# 7seg.net
KiCad netlist of a schematic drawn in EAGLE
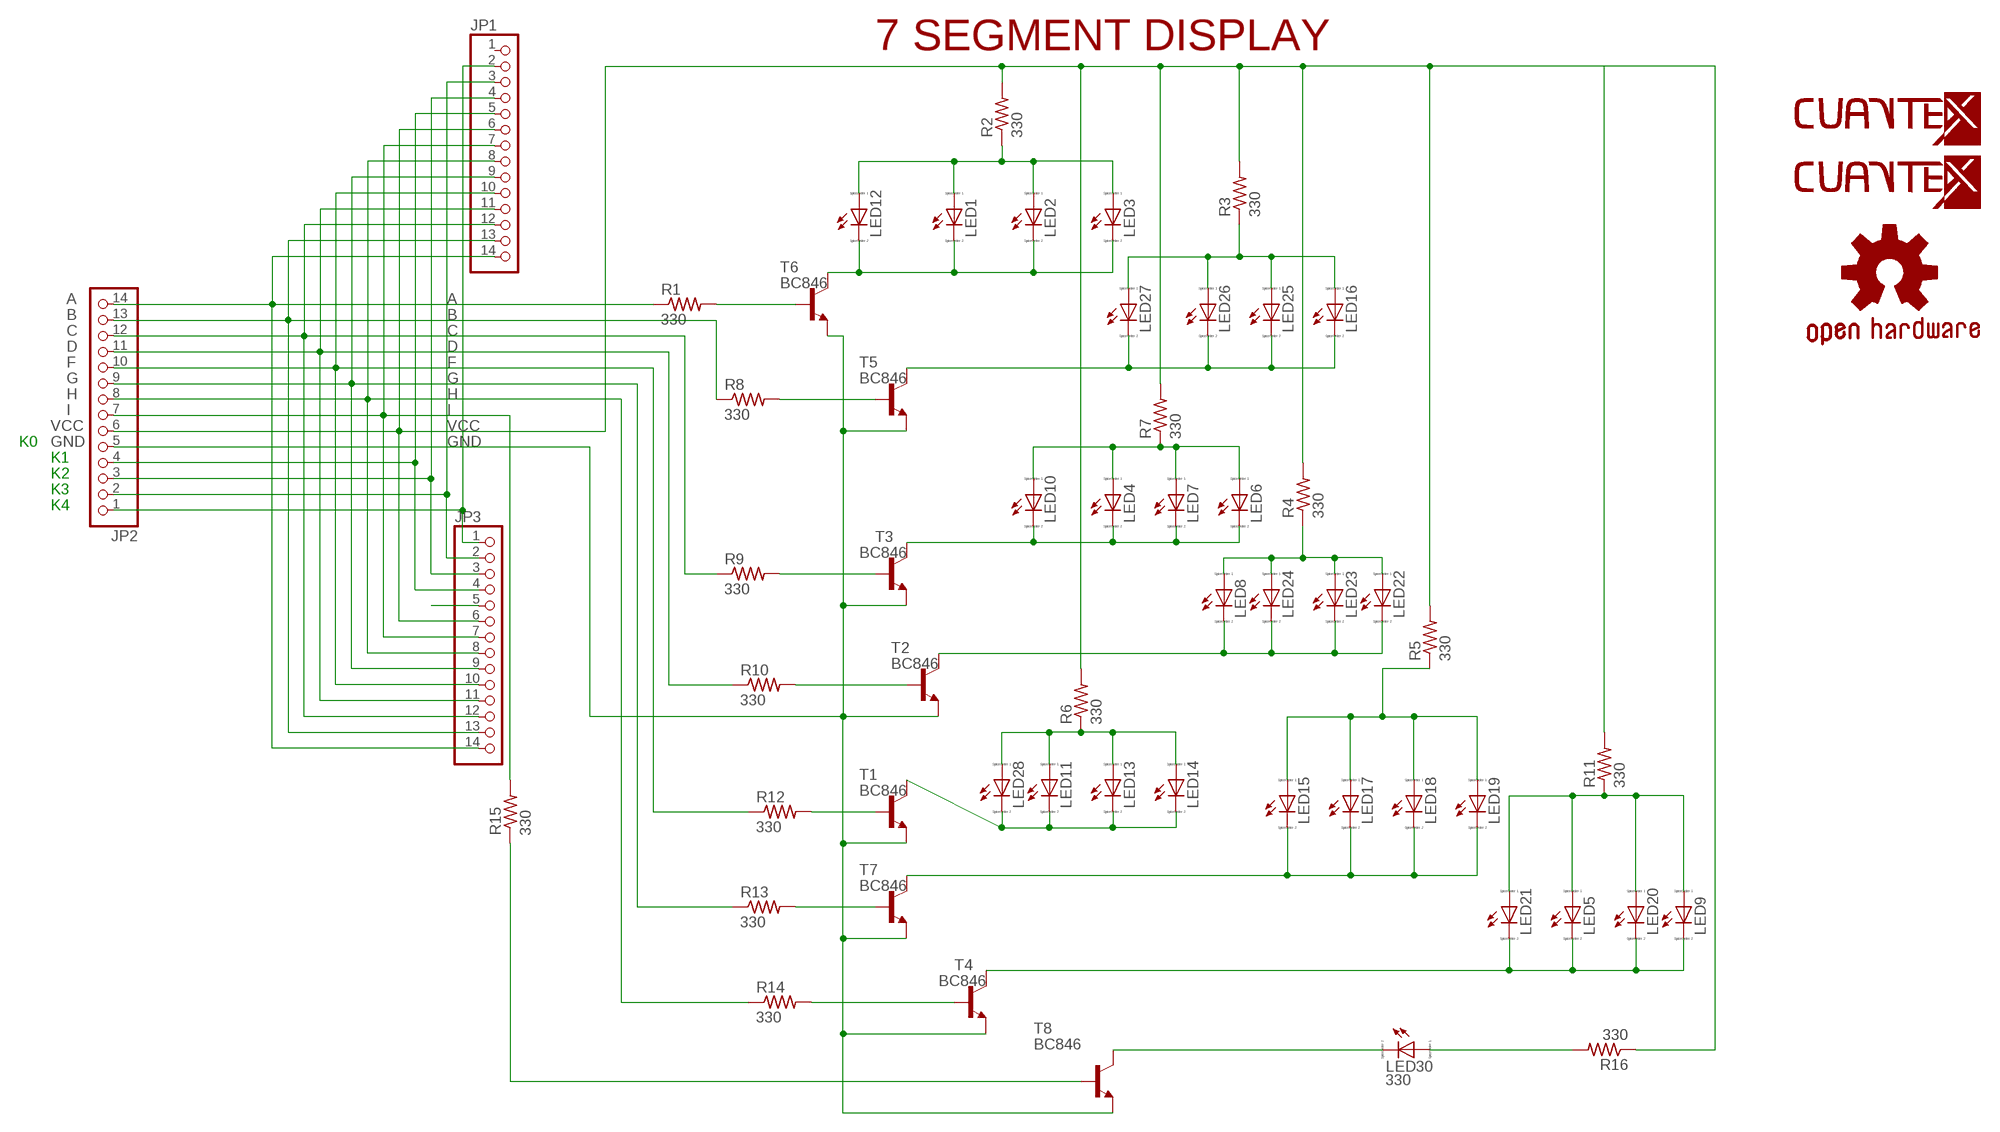
[diagram p0: schematic, sheet 1]

(export (version "E")
  (design (tool "Eeschema 10.0.6"))
  (components
    (comp (ref "GOLD_ORB_SM2")
      (value "OSHWLOGO_GOLD_ORB_MED")
      (footprint "eagle-import:OSHW1")
      (libsource (lib "eagle-import") (part "OSHWLOGO_GOLD_ORB_MED"))
    )
    (comp (ref "JP1")
      (value "PINHD-1X14")
      (footprint "eagle-import:1X14")
      (libsource (lib "eagle-import") (part "PINHD-1X14"))
    )
    (comp (ref "JP2")
      (value "PINHD-1X14")
      (footprint "eagle-import:1X14")
      (libsource (lib "eagle-import") (part "PINHD-1X14"))
    )
    (comp (ref "JP3")
      (value "PINHD-1X14")
      (footprint "eagle-import:1X14")
      (libsource (lib "eagle-import") (part "PINHD-1X14"))
    )
    (comp (ref "LED1")
      (value "LED_E")
      (footprint "eagle-import:LED_1206")
      (libsource (lib "eagle-import") (part "LED_E"))
    )
    (comp (ref "LED2")
      (value "LED_E")
      (footprint "eagle-import:LED_1206")
      (libsource (lib "eagle-import") (part "LED_E"))
    )
    (comp (ref "LED3")
      (value "LED_E")
      (footprint "eagle-import:LED_1206")
      (libsource (lib "eagle-import") (part "LED_E"))
    )
    (comp (ref "LED4")
      (value "LED_E")
      (footprint "eagle-import:LED_1206")
      (libsource (lib "eagle-import") (part "LED_E"))
    )
    (comp (ref "LED5")
      (value "LED_E")
      (footprint "eagle-import:LED_1206")
      (libsource (lib "eagle-import") (part "LED_E"))
    )
    (comp (ref "LED6")
      (value "LED_E")
      (footprint "eagle-import:LED_1206")
      (libsource (lib "eagle-import") (part "LED_E"))
    )
    (comp (ref "LED7")
      (value "LED_E")
      (footprint "eagle-import:LED_1206")
      (libsource (lib "eagle-import") (part "LED_E"))
    )
    (comp (ref "LED8")
      (value "LED_E")
      (footprint "eagle-import:LED_1206")
      (libsource (lib "eagle-import") (part "LED_E"))
    )
    (comp (ref "LED9")
      (value "LED_E")
      (footprint "eagle-import:LED_1206")
      (libsource (lib "eagle-import") (part "LED_E"))
    )
    (comp (ref "LED10")
      (value "LED_E")
      (footprint "eagle-import:LED_1206")
      (libsource (lib "eagle-import") (part "LED_E"))
    )
    (comp (ref "LED11")
      (value "LED_E")
      (footprint "eagle-import:LED_1206")
      (libsource (lib "eagle-import") (part "LED_E"))
    )
    (comp (ref "LED12")
      (value "LED_E")
      (footprint "eagle-import:LED_1206")
      (libsource (lib "eagle-import") (part "LED_E"))
    )
    (comp (ref "LED13")
      (value "LED_E")
      (footprint "eagle-import:LED_1206")
      (libsource (lib "eagle-import") (part "LED_E"))
    )
    (comp (ref "LED14")
      (value "LED_E")
      (footprint "eagle-import:LED_1206")
      (libsource (lib "eagle-import") (part "LED_E"))
    )
    (comp (ref "LED15")
      (value "LED_E")
      (footprint "eagle-import:LED_1206")
      (libsource (lib "eagle-import") (part "LED_E"))
    )
    (comp (ref "LED16")
      (value "LED_E")
      (footprint "eagle-import:LED_1206")
      (libsource (lib "eagle-import") (part "LED_E"))
    )
    (comp (ref "LED17")
      (value "LED_E")
      (footprint "eagle-import:LED_1206")
      (libsource (lib "eagle-import") (part "LED_E"))
    )
    (comp (ref "LED18")
      (value "LED_E")
      (footprint "eagle-import:LED_1206")
      (libsource (lib "eagle-import") (part "LED_E"))
    )
    (comp (ref "LED19")
      (value "LED_E")
      (footprint "eagle-import:LED_1206")
      (libsource (lib "eagle-import") (part "LED_E"))
    )
    (comp (ref "LED20")
      (value "LED_E")
      (footprint "eagle-import:LED_1206")
      (libsource (lib "eagle-import") (part "LED_E"))
    )
    (comp (ref "LED21")
      (value "LED_E")
      (footprint "eagle-import:LED_1206")
      (libsource (lib "eagle-import") (part "LED_E"))
    )
    (comp (ref "LED22")
      (value "LED_E")
      (footprint "eagle-import:LED_1206")
      (libsource (lib "eagle-import") (part "LED_E"))
    )
    (comp (ref "LED23")
      (value "LED_E")
      (footprint "eagle-import:LED_1206")
      (libsource (lib "eagle-import") (part "LED_E"))
    )
    (comp (ref "LED24")
      (value "LED_E")
      (footprint "eagle-import:LED_1206")
      (libsource (lib "eagle-import") (part "LED_E"))
    )
    (comp (ref "LED25")
      (value "LED_E")
      (footprint "eagle-import:LED_1206")
      (libsource (lib "eagle-import") (part "LED_E"))
    )
    (comp (ref "LED26")
      (value "LED_E")
      (footprint "eagle-import:LED_1206")
      (libsource (lib "eagle-import") (part "LED_E"))
    )
    (comp (ref "LED27")
      (value "LED_E")
      (footprint "eagle-import:LED_1206")
      (libsource (lib "eagle-import") (part "LED_E"))
    )
    (comp (ref "LED28")
      (value "LED_E")
      (footprint "eagle-import:LED_1206")
      (libsource (lib "eagle-import") (part "LED_E"))
    )
    (comp (ref "LED30")
      (value "330")
      (footprint "eagle-import:LED_1206")
      (libsource (lib "eagle-import") (part "LED_E"))
    )
    (comp (ref "R1")
      (value "330")
      (footprint "eagle-import:R0603")
      (libsource (lib "eagle-import") (part "resistor_R-US_R0603"))
    )
    (comp (ref "R2")
      (value "330")
      (footprint "eagle-import:R0603")
      (libsource (lib "eagle-import") (part "resistor_R-US_R0603"))
    )
    (comp (ref "R3")
      (value "330")
      (footprint "eagle-import:R0603")
      (libsource (lib "eagle-import") (part "resistor_R-US_R0603"))
    )
    (comp (ref "R4")
      (value "330")
      (footprint "eagle-import:R0603")
      (libsource (lib "eagle-import") (part "resistor_R-US_R0603"))
    )
    (comp (ref "R5")
      (value "330")
      (footprint "eagle-import:R0603")
      (libsource (lib "eagle-import") (part "resistor_R-US_R0603"))
    )
    (comp (ref "R6")
      (value "330")
      (footprint "eagle-import:R0603")
      (libsource (lib "eagle-import") (part "resistor_R-US_R0603"))
    )
    (comp (ref "R7")
      (value "330")
      (footprint "eagle-import:R0603")
      (libsource (lib "eagle-import") (part "resistor_R-US_R0603"))
    )
    (comp (ref "R8")
      (value "330")
      (footprint "eagle-import:R0603")
      (libsource (lib "eagle-import") (part "resistor_R-US_R0603"))
    )
    (comp (ref "R9")
      (value "330")
      (footprint "eagle-import:R0603")
      (libsource (lib "eagle-import") (part "resistor_R-US_R0603"))
    )
    (comp (ref "R10")
      (value "330")
      (footprint "eagle-import:R0603")
      (libsource (lib "eagle-import") (part "resistor_R-US_R0603"))
    )
    (comp (ref "R11")
      (value "330")
      (footprint "eagle-import:R0603")
      (libsource (lib "eagle-import") (part "resistor_R-US_R0603"))
    )
    (comp (ref "R12")
      (value "330")
      (footprint "eagle-import:R0603")
      (libsource (lib "eagle-import") (part "resistor_R-US_R0603"))
    )
    (comp (ref "R13")
      (value "330")
      (footprint "eagle-import:R0603")
      (libsource (lib "eagle-import") (part "resistor_R-US_R0603"))
    )
    (comp (ref "R14")
      (value "330")
      (footprint "eagle-import:R0603")
      (libsource (lib "eagle-import") (part "resistor_R-US_R0603"))
    )
    (comp (ref "R15")
      (value "330")
      (footprint "eagle-import:R0603")
      (libsource (lib "eagle-import") (part "R-US_R0603"))
    )
    (comp (ref "R16")
      (value "330")
      (footprint "eagle-import:R0603")
      (libsource (lib "eagle-import") (part "R-US_R0603"))
    )
    (comp (ref "T1")
      (value "BC846")
      (footprint "eagle-import:SOT23")
      (libsource (lib "eagle-import") (part "BC846"))
    )
    (comp (ref "T2")
      (value "BC846")
      (footprint "eagle-import:SOT23")
      (libsource (lib "eagle-import") (part "transistor-neu-to92_BC846"))
    )
    (comp (ref "T3")
      (value "BC846")
      (footprint "eagle-import:SOT23")
      (libsource (lib "eagle-import") (part "transistor-neu-to92_BC846"))
    )
    (comp (ref "T4")
      (value "BC846")
      (footprint "eagle-import:SOT23")
      (libsource (lib "eagle-import") (part "transistor-neu-to92_BC846"))
    )
    (comp (ref "T5")
      (value "BC846")
      (footprint "eagle-import:SOT23")
      (libsource (lib "eagle-import") (part "transistor-neu-to92_BC846"))
    )
    (comp (ref "T6")
      (value "BC846")
      (footprint "eagle-import:SOT23")
      (libsource (lib "eagle-import") (part "transistor-neu-to92_BC846"))
    )
    (comp (ref "T7")
      (value "BC846")
      (footprint "eagle-import:SOT23")
      (libsource (lib "eagle-import") (part "transistor-neu-to92_BC846"))
    )
    (comp (ref "T8")
      (value "BC846")
      (footprint "eagle-import:SOT23")
      (libsource (lib "eagle-import") (part "transistor-neu-to92_BC846"))
    )
    (comp (ref "U$1")
      (value "LOGO-TOP-20MM")
      (footprint "eagle-import:C-0")
      (libsource (lib "eagle-import") (part "LOGO-TOP-20MM"))
    )
    (comp (ref "U$2")
      (value "LOGO-BOT-60MM")
      (footprint "eagle-import:B-60")
      (libsource (lib "eagle-import") (part "LOGO-BOT-60MM"))
    )
  )
  (nets
    (net (code "1") (name "/A") (class "Default")
      (node (ref "JP1") (pin "14") (pinfunction "14_14") (pintype "passive"))
      (node (ref "JP2") (pin "14") (pinfunction "14_14") (pintype "passive"))
      (node (ref "JP3") (pin "14") (pinfunction "14_14") (pintype "passive"))
      (node (ref "R1") (pin "1") (pinfunction "1_1") (pintype "passive"))
    )
    (net (code "2") (name "/B") (class "Default")
      (node (ref "JP1") (pin "13") (pinfunction "13_13") (pintype "passive"))
      (node (ref "JP2") (pin "13") (pinfunction "13_13") (pintype "passive"))
      (node (ref "JP3") (pin "13") (pinfunction "13_13") (pintype "passive"))
      (node (ref "R8") (pin "1") (pinfunction "1_1") (pintype "passive"))
    )
    (net (code "3") (name "/C") (class "Default")
      (node (ref "JP1") (pin "12") (pinfunction "12_12") (pintype "passive"))
      (node (ref "JP2") (pin "12") (pinfunction "12_12") (pintype "passive"))
      (node (ref "JP3") (pin "12") (pinfunction "12_12") (pintype "passive"))
      (node (ref "R9") (pin "1") (pinfunction "1_1") (pintype "passive"))
    )
    (net (code "4") (name "/D") (class "Default")
      (node (ref "JP1") (pin "11") (pinfunction "11_11") (pintype "passive"))
      (node (ref "JP2") (pin "11") (pinfunction "11_11") (pintype "passive"))
      (node (ref "JP3") (pin "11") (pinfunction "11_11") (pintype "passive"))
      (node (ref "R10") (pin "1") (pinfunction "1_1") (pintype "passive"))
    )
    (net (code "5") (name "/F") (class "Default")
      (node (ref "JP1") (pin "10") (pinfunction "10_10") (pintype "passive"))
      (node (ref "JP2") (pin "10") (pinfunction "10_10") (pintype "passive"))
      (node (ref "JP3") (pin "10") (pinfunction "10_10") (pintype "passive"))
      (node (ref "R12") (pin "1") (pinfunction "1_1") (pintype "passive"))
    )
    (net (code "6") (name "/G") (class "Default")
      (node (ref "JP1") (pin "9") (pinfunction "9_9") (pintype "passive"))
      (node (ref "JP2") (pin "9") (pinfunction "9_9") (pintype "passive"))
      (node (ref "JP3") (pin "9") (pinfunction "9_9") (pintype "passive"))
      (node (ref "R13") (pin "1") (pinfunction "1_1") (pintype "passive"))
    )
    (net (code "7") (name "/GND") (class "Default")
      (node (ref "JP2") (pin "5") (pinfunction "5_5") (pintype "passive"))
      (node (ref "JP3") (pin "5") (pinfunction "5_5") (pintype "passive"))
      (node (ref "T1") (pin "2") (pinfunction "E_2") (pintype "passive"))
      (node (ref "T2") (pin "2") (pinfunction "E_2") (pintype "passive"))
      (node (ref "T3") (pin "2") (pinfunction "E_2") (pintype "passive"))
      (node (ref "T4") (pin "2") (pinfunction "E_2") (pintype "passive"))
      (node (ref "T5") (pin "2") (pinfunction "E_2") (pintype "passive"))
      (node (ref "T6") (pin "2") (pinfunction "E_2") (pintype "passive"))
      (node (ref "T7") (pin "2") (pinfunction "E_2") (pintype "passive"))
      (node (ref "T8") (pin "2") (pinfunction "E_2") (pintype "passive"))
    )
    (net (code "8") (name "/H") (class "Default")
      (node (ref "JP1") (pin "8") (pinfunction "8_8") (pintype "passive"))
      (node (ref "JP2") (pin "8") (pinfunction "8_8") (pintype "passive"))
      (node (ref "JP3") (pin "8") (pinfunction "8_8") (pintype "passive"))
      (node (ref "R14") (pin "1") (pinfunction "1_1") (pintype "passive"))
    )
    (net (code "9") (name "/I") (class "Default")
      (node (ref "JP1") (pin "7") (pinfunction "7_7") (pintype "passive"))
      (node (ref "JP2") (pin "7") (pinfunction "7_7") (pintype "passive"))
      (node (ref "JP3") (pin "7") (pinfunction "7_7") (pintype "passive"))
      (node (ref "R15") (pin "2") (pinfunction "2_2") (pintype "passive"))
    )
    (net (code "10") (name "/VCC") (class "Default")
      (node (ref "JP1") (pin "6") (pinfunction "6_6") (pintype "passive"))
      (node (ref "JP2") (pin "6") (pinfunction "6_6") (pintype "passive"))
      (node (ref "JP3") (pin "6") (pinfunction "6_6") (pintype "passive"))
      (node (ref "R11") (pin "2") (pinfunction "2_2") (pintype "passive"))
      (node (ref "R16") (pin "1") (pinfunction "1_1") (pintype "passive"))
      (node (ref "R2") (pin "2") (pinfunction "2_2") (pintype "passive"))
      (node (ref "R3") (pin "2") (pinfunction "2_2") (pintype "passive"))
      (node (ref "R4") (pin "2") (pinfunction "2_2") (pintype "passive"))
      (node (ref "R5") (pin "2") (pinfunction "2_2") (pintype "passive"))
      (node (ref "R6") (pin "2") (pinfunction "2_2") (pintype "passive"))
      (node (ref "R7") (pin "2") (pinfunction "2_2") (pintype "passive"))
    )
    (net (code "11") (name "Net-(JP1-Pad2)") (class "Default")
      (node (ref "JP1") (pin "2") (pinfunction "2_2") (pintype "passive"))
      (node (ref "JP2") (pin "1") (pinfunction "1_1") (pintype "passive"))
      (node (ref "JP3") (pin "1") (pinfunction "1_1") (pintype "passive"))
    )
    (net (code "12") (name "Net-(JP1-Pad3)") (class "Default")
      (node (ref "JP1") (pin "3") (pinfunction "3_3") (pintype "passive"))
      (node (ref "JP2") (pin "2") (pinfunction "2_2") (pintype "passive"))
      (node (ref "JP3") (pin "2") (pinfunction "2_2") (pintype "passive"))
    )
    (net (code "13") (name "Net-(JP1-Pad4)") (class "Default")
      (node (ref "JP1") (pin "4") (pinfunction "4_4") (pintype "passive"))
      (node (ref "JP2") (pin "3") (pinfunction "3_3") (pintype "passive"))
      (node (ref "JP3") (pin "3") (pinfunction "3_3") (pintype "passive"))
    )
    (net (code "14") (name "Net-(JP1-Pad5)") (class "Default")
      (node (ref "JP1") (pin "5") (pinfunction "5_5") (pintype "passive"))
      (node (ref "JP2") (pin "4") (pinfunction "4_4") (pintype "passive"))
      (node (ref "JP3") (pin "4") (pinfunction "4_4") (pintype "passive"))
    )
    (net (code "15") (name "Net-(LED1-PadA)") (class "Default")
      (node (ref "LED1") (pin "A") (pinfunction "A_A") (pintype "passive"))
      (node (ref "LED12") (pin "A") (pinfunction "A_A") (pintype "passive"))
      (node (ref "LED2") (pin "A") (pinfunction "A_A") (pintype "passive"))
      (node (ref "LED3") (pin "A") (pinfunction "A_A") (pintype "passive"))
      (node (ref "R2") (pin "1") (pinfunction "1_1") (pintype "passive"))
    )
    (net (code "16") (name "Net-(LED10-PadA)") (class "Default")
      (node (ref "LED10") (pin "A") (pinfunction "A_A") (pintype "passive"))
      (node (ref "LED4") (pin "A") (pinfunction "A_A") (pintype "passive"))
      (node (ref "LED6") (pin "A") (pinfunction "A_A") (pintype "passive"))
      (node (ref "LED7") (pin "A") (pinfunction "A_A") (pintype "passive"))
      (node (ref "R7") (pin "1") (pinfunction "1_1") (pintype "passive"))
    )
    (net (code "17") (name "Net-(LED11-PadA)") (class "Default")
      (node (ref "LED11") (pin "A") (pinfunction "A_A") (pintype "passive"))
      (node (ref "LED13") (pin "A") (pinfunction "A_A") (pintype "passive"))
      (node (ref "LED14") (pin "A") (pinfunction "A_A") (pintype "passive"))
      (node (ref "LED28") (pin "A") (pinfunction "A_A") (pintype "passive"))
      (node (ref "R6") (pin "1") (pinfunction "1_1") (pintype "passive"))
    )
    (net (code "18") (name "Net-(LED15-PadA)") (class "Default")
      (node (ref "LED15") (pin "A") (pinfunction "A_A") (pintype "passive"))
      (node (ref "LED17") (pin "A") (pinfunction "A_A") (pintype "passive"))
      (node (ref "LED18") (pin "A") (pinfunction "A_A") (pintype "passive"))
      (node (ref "LED19") (pin "A") (pinfunction "A_A") (pintype "passive"))
      (node (ref "R5") (pin "1") (pinfunction "1_1") (pintype "passive"))
    )
    (net (code "19") (name "Net-(LED16-PadA)") (class "Default")
      (node (ref "LED16") (pin "A") (pinfunction "A_A") (pintype "passive"))
      (node (ref "LED25") (pin "A") (pinfunction "A_A") (pintype "passive"))
      (node (ref "LED26") (pin "A") (pinfunction "A_A") (pintype "passive"))
      (node (ref "LED27") (pin "A") (pinfunction "A_A") (pintype "passive"))
      (node (ref "R3") (pin "1") (pinfunction "1_1") (pintype "passive"))
    )
    (net (code "20") (name "Net-(LED20-PadA)") (class "Default")
      (node (ref "LED20") (pin "A") (pinfunction "A_A") (pintype "passive"))
      (node (ref "LED21") (pin "A") (pinfunction "A_A") (pintype "passive"))
      (node (ref "LED5") (pin "A") (pinfunction "A_A") (pintype "passive"))
      (node (ref "LED9") (pin "A") (pinfunction "A_A") (pintype "passive"))
      (node (ref "R11") (pin "1") (pinfunction "1_1") (pintype "passive"))
    )
    (net (code "21") (name "Net-(LED22-PadA)") (class "Default")
      (node (ref "LED22") (pin "A") (pinfunction "A_A") (pintype "passive"))
      (node (ref "LED23") (pin "A") (pinfunction "A_A") (pintype "passive"))
      (node (ref "LED24") (pin "A") (pinfunction "A_A") (pintype "passive"))
      (node (ref "LED8") (pin "A") (pinfunction "A_A") (pintype "passive"))
      (node (ref "R4") (pin "1") (pinfunction "1_1") (pintype "passive"))
    )
    (net (code "22") (name "Net-(LED30-PadA)") (class "Default")
      (node (ref "LED30") (pin "A") (pinfunction "A_A") (pintype "passive"))
      (node (ref "R16") (pin "2") (pinfunction "2_2") (pintype "passive"))
    )
    (net (code "23") (name "Net-(T1-B)") (class "Default")
      (node (ref "R12") (pin "2") (pinfunction "2_2") (pintype "passive"))
      (node (ref "T1") (pin "1") (pinfunction "B_1") (pintype "passive"))
    )
    (net (code "24") (name "Net-(T1-C)") (class "Default")
      (node (ref "LED11") (pin "C") (pinfunction "C_C") (pintype "passive"))
      (node (ref "LED13") (pin "C") (pinfunction "C_C") (pintype "passive"))
      (node (ref "LED14") (pin "C") (pinfunction "C_C") (pintype "passive"))
      (node (ref "LED28") (pin "C") (pinfunction "C_C") (pintype "passive"))
      (node (ref "T1") (pin "3") (pinfunction "C_3") (pintype "passive"))
    )
    (net (code "25") (name "Net-(T2-B)") (class "Default")
      (node (ref "R10") (pin "2") (pinfunction "2_2") (pintype "passive"))
      (node (ref "T2") (pin "1") (pinfunction "B_1") (pintype "passive"))
    )
    (net (code "26") (name "Net-(T2-C)") (class "Default")
      (node (ref "LED22") (pin "C") (pinfunction "C_C") (pintype "passive"))
      (node (ref "LED23") (pin "C") (pinfunction "C_C") (pintype "passive"))
      (node (ref "LED24") (pin "C") (pinfunction "C_C") (pintype "passive"))
      (node (ref "LED8") (pin "C") (pinfunction "C_C") (pintype "passive"))
      (node (ref "T2") (pin "3") (pinfunction "C_3") (pintype "passive"))
    )
    (net (code "27") (name "Net-(T3-B)") (class "Default")
      (node (ref "R9") (pin "2") (pinfunction "2_2") (pintype "passive"))
      (node (ref "T3") (pin "1") (pinfunction "B_1") (pintype "passive"))
    )
    (net (code "28") (name "Net-(T3-C)") (class "Default")
      (node (ref "LED10") (pin "C") (pinfunction "C_C") (pintype "passive"))
      (node (ref "LED4") (pin "C") (pinfunction "C_C") (pintype "passive"))
      (node (ref "LED6") (pin "C") (pinfunction "C_C") (pintype "passive"))
      (node (ref "LED7") (pin "C") (pinfunction "C_C") (pintype "passive"))
      (node (ref "T3") (pin "3") (pinfunction "C_3") (pintype "passive"))
    )
    (net (code "29") (name "Net-(T4-B)") (class "Default")
      (node (ref "R14") (pin "2") (pinfunction "2_2") (pintype "passive"))
      (node (ref "T4") (pin "1") (pinfunction "B_1") (pintype "passive"))
    )
    (net (code "30") (name "Net-(T4-C)") (class "Default")
      (node (ref "LED20") (pin "C") (pinfunction "C_C") (pintype "passive"))
      (node (ref "LED21") (pin "C") (pinfunction "C_C") (pintype "passive"))
      (node (ref "LED5") (pin "C") (pinfunction "C_C") (pintype "passive"))
      (node (ref "LED9") (pin "C") (pinfunction "C_C") (pintype "passive"))
      (node (ref "T4") (pin "3") (pinfunction "C_3") (pintype "passive"))
    )
    (net (code "31") (name "Net-(T5-B)") (class "Default")
      (node (ref "R8") (pin "2") (pinfunction "2_2") (pintype "passive"))
      (node (ref "T5") (pin "1") (pinfunction "B_1") (pintype "passive"))
    )
    (net (code "32") (name "Net-(T5-C)") (class "Default")
      (node (ref "LED16") (pin "C") (pinfunction "C_C") (pintype "passive"))
      (node (ref "LED25") (pin "C") (pinfunction "C_C") (pintype "passive"))
      (node (ref "LED26") (pin "C") (pinfunction "C_C") (pintype "passive"))
      (node (ref "LED27") (pin "C") (pinfunction "C_C") (pintype "passive"))
      (node (ref "T5") (pin "3") (pinfunction "C_3") (pintype "passive"))
    )
    (net (code "33") (name "Net-(T6-B)") (class "Default")
      (node (ref "R1") (pin "2") (pinfunction "2_2") (pintype "passive"))
      (node (ref "T6") (pin "1") (pinfunction "B_1") (pintype "passive"))
    )
    (net (code "34") (name "Net-(T6-C)") (class "Default")
      (node (ref "LED1") (pin "C") (pinfunction "C_C") (pintype "passive"))
      (node (ref "LED12") (pin "C") (pinfunction "C_C") (pintype "passive"))
      (node (ref "LED2") (pin "C") (pinfunction "C_C") (pintype "passive"))
      (node (ref "LED3") (pin "C") (pinfunction "C_C") (pintype "passive"))
      (node (ref "T6") (pin "3") (pinfunction "C_3") (pintype "passive"))
    )
    (net (code "35") (name "Net-(T7-B)") (class "Default")
      (node (ref "R13") (pin "2") (pinfunction "2_2") (pintype "passive"))
      (node (ref "T7") (pin "1") (pinfunction "B_1") (pintype "passive"))
    )
    (net (code "36") (name "Net-(T7-C)") (class "Default")
      (node (ref "LED15") (pin "C") (pinfunction "C_C") (pintype "passive"))
      (node (ref "LED17") (pin "C") (pinfunction "C_C") (pintype "passive"))
      (node (ref "LED18") (pin "C") (pinfunction "C_C") (pintype "passive"))
      (node (ref "LED19") (pin "C") (pinfunction "C_C") (pintype "passive"))
      (node (ref "T7") (pin "3") (pinfunction "C_3") (pintype "passive"))
    )
    (net (code "37") (name "Net-(T8-B)") (class "Default")
      (node (ref "R15") (pin "1") (pinfunction "1_1") (pintype "passive"))
      (node (ref "T8") (pin "1") (pinfunction "B_1") (pintype "passive"))
    )
    (net (code "38") (name "Net-(T8-C)") (class "Default")
      (node (ref "LED30") (pin "C") (pinfunction "C_C") (pintype "passive"))
      (node (ref "T8") (pin "3") (pinfunction "C_3") (pintype "passive"))
    )
    (net (code "39") (name "unconnected-(JP1-Pad1)") (class "Default")
      (node (ref "JP1") (pin "1") (pinfunction "1_1") (pintype "passive"))
    )
  )
)
